# XL4016.net
KiCad netlist of a schematic drawn in Altium Designer
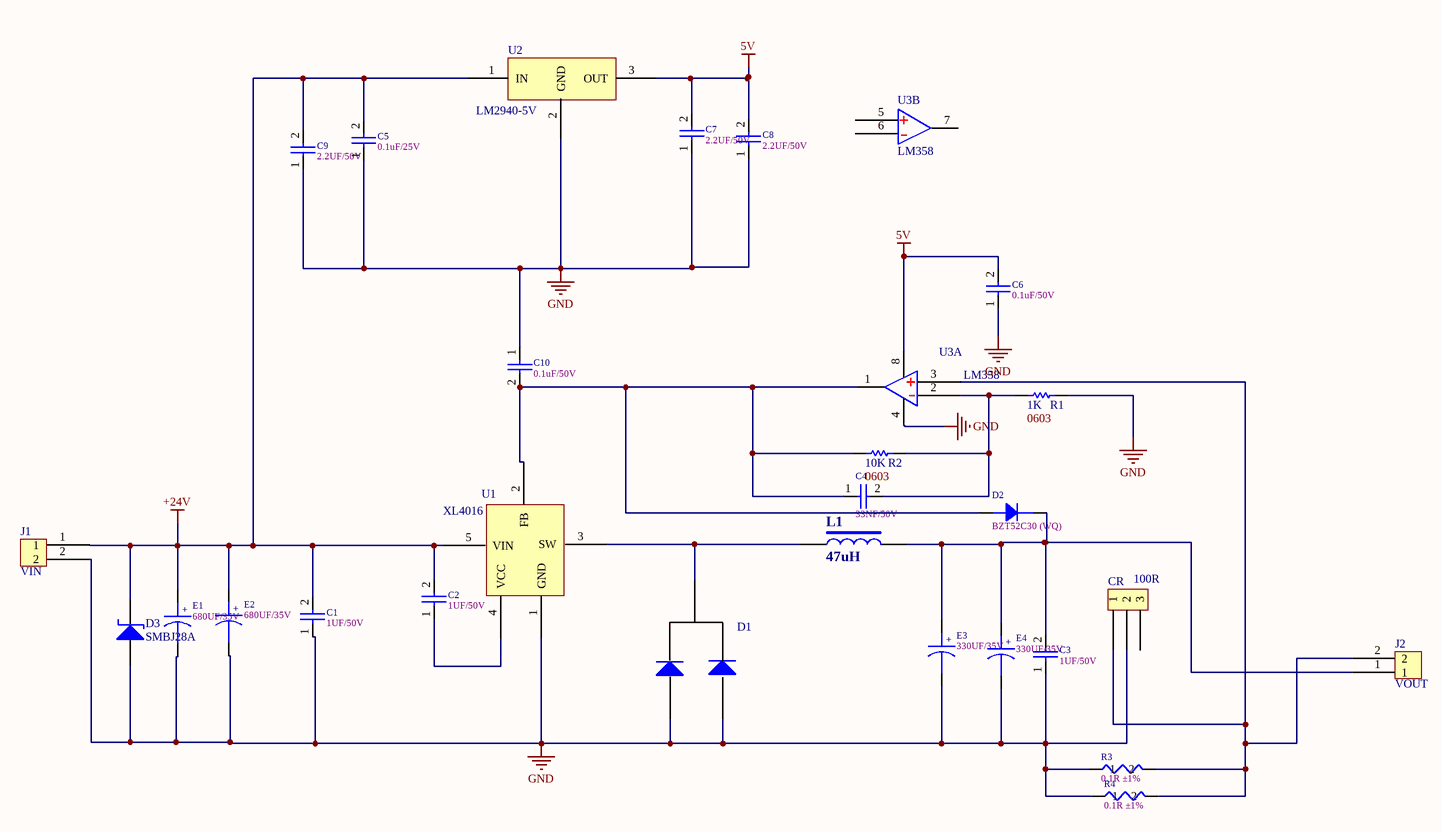
[diagram p0: XL4016.SchDoc]

(export (version "E")
  (design (tool "Eeschema 10.0.6"))
  (components
    (comp (ref "C1")
      (value "1UF/50V")
      (footprint "C0805")
      (description "Capacitor")
      (libsource (lib "清洗机旋钮开关") (part "CAP_5"))
    )
    (comp (ref "C2")
      (value "1UF/50V")
      (footprint "C0805")
      (description "Capacitor")
      (libsource (lib "清洗机旋钮开关") (part "CAP_5"))
    )
    (comp (ref "C3")
      (value "1UF/50V")
      (footprint "C0805")
      (description "Capacitor")
      (libsource (lib "清洗机旋钮开关") (part "CAP_5"))
    )
    (comp (ref "C4")
      (value "33NF/50V")
      (footprint "C0603")
      (description "Capacitor")
      (libsource (lib "清洗机旋钮开关") (part "CAP"))
    )
    (comp (ref "C5")
      (value "0.1uF/25V")
      (footprint "C0603")
      (description "Capacitor")
      (libsource (lib "清洗机旋钮开关") (part "CAP"))
    )
    (comp (ref "C6")
      (value "0.1uF/50V")
      (footprint "C0603")
      (description "Capacitor")
      (libsource (lib "清洗机旋钮开关") (part "CAP"))
    )
    (comp (ref "C7")
      (value "2.2UF/50V")
      (footprint "C0805")
      (description "Capacitor")
      (libsource (lib "清洗机旋钮开关") (part "CAP_5"))
    )
    (comp (ref "C8")
      (value "2.2UF/50V")
      (footprint "C0805")
      (description "Capacitor")
      (libsource (lib "清洗机旋钮开关") (part "CAP_5"))
    )
    (comp (ref "C9")
      (value "2.2UF/50V")
      (footprint "C0805")
      (description "Capacitor")
      (libsource (lib "清洗机旋钮开关") (part "CAP_5"))
    )
    (comp (ref "C10")
      (value "0.1uF/50V")
      (footprint "C0603")
      (description "Capacitor")
      (libsource (lib "清洗机旋钮开关") (part "CAP"))
    )
    (comp (ref "CR") (value "100R") (footprint "3296W") (libsource (lib "VR") (part "RV")))
    (comp (ref "D1") (value "Schottky") (footprint "TO-2520") (libsource (lib "SCHOTTKY") (part "Schottky")))
    (comp (ref "D2")
      (value "BZT52C30 (WQ)")
      (footprint "SOD123")
      (description "Diode")
      (libsource (lib "清洗固化") (part "DIODE._1"))
    )
    (comp (ref "D3") (value "SMBJ28A") (footprint "DO214AA") (libsource (lib "清洗机旋钮开关") (part "TVS")))
    (comp (ref "E1")
      (value "680UF/35V")
      (footprint "C10X17")
      (description "Capacitor")
      (libsource (lib "TL494-BOOST") (part "CAPACITOR POL"))
    )
    (comp (ref "E2")
      (value "680UF/35V")
      (footprint "C10X17")
      (description "Capacitor")
      (libsource (lib "TL494-BOOST") (part "CAPACITOR POL"))
    )
    (comp (ref "E3")
      (value "330UF/35V")
      (footprint "C10X17")
      (description "Capacitor")
      (libsource (lib "TL494-BOOST") (part "CAPACITOR POL"))
    )
    (comp (ref "E4")
      (value "330UF/35V")
      (footprint "C10X17")
      (description "Capacitor")
      (libsource (lib "TL494-BOOST") (part "CAPACITOR POL"))
    )
    (comp (ref "J1") (value "VIN") (footprint "VH3.96_2WP") (libsource (lib "") (part "VH3.96_2P_1")))
    (comp (ref "J2")
      (value "VOUT")
      (footprint "VH3.96_2WP")
      (libsource (lib "VVH3.96_2P") (part "VH3.96_2P"))
    )
    (comp (ref "L1") (value "47uH") (footprint "L24x10") (libsource (lib "清洗机旋钮开关") (part "INDUCTOR2")))
    (comp (ref "R1")
      (value "1K")
      (footprint "0603")
      (description "Resistor")
      (fields (field (name "PUBLISHER") "Altium Limited"))
      (libsource (lib "清洗机旋钮开关") (part "Res1_4"))
    )
    (comp (ref "R2")
      (value "10K")
      (footprint "0603")
      (description "Resistor")
      (fields (field (name "PUBLISHER") "Altium Limited"))
      (libsource (lib "清洗机旋钮开关") (part "Res1_4"))
    )
    (comp (ref "R3")
      (value "0.1R ±1%")
      (footprint "R1206")
      (libsource (lib "MARS2-PRO20201214") (part "RES"))
    )
    (comp (ref "R4")
      (value "0.1R ±1%")
      (footprint "R1206")
      (libsource (lib "MARS2-PRO20201214") (part "RES"))
    )
    (comp (ref "U1") (value "XL4016") (footprint "TO220-5L") (libsource (lib "XL4016") (part "XL4016")))
    (comp (ref "U2")
      (value "LM2940-5V")
      (footprint "SOT-223")
      (libsource (lib "LM2940-5V") (part "LM2940-5V"))
    )
    (comp (ref "U3") (value "LM358") (footprint "SOP8L") (libsource (lib "LM358D") (part "LM358")))
  )
  (nets
    (net (code "1") (name "+24V") (class "Default")
      (node (ref "C1") (pin "2") (pinfunction "2_2") (pintype "passive"))
      (node (ref "C2") (pin "2") (pinfunction "2_2") (pintype "passive"))
      (node (ref "C5") (pin "2") (pinfunction "2_2") (pintype "passive"))
      (node (ref "C9") (pin "2") (pinfunction "2_2") (pintype "passive"))
      (node (ref "D3") (pin "2") (pinfunction "K_2") (pintype "passive"))
      (node (ref "E1") (pin "1") (pinfunction "1_1") (pintype "passive"))
      (node (ref "E2") (pin "1") (pinfunction "1_1") (pintype "passive"))
      (node (ref "J1") (pin "1") (pinfunction "1_1") (pintype "passive"))
      (node (ref "U1") (pin "5") (pinfunction "VIN_5") (pintype "passive"))
      (node (ref "U2") (pin "1") (pinfunction "IN_1") (pintype "passive"))
    )
    (net (code "2") (name "5V") (class "Default")
      (node (ref "C6") (pin "2") (pinfunction "2_2") (pintype "passive"))
      (node (ref "C7") (pin "2") (pinfunction "2_2") (pintype "passive"))
      (node (ref "C8") (pin "2") (pinfunction "2_2") (pintype "passive"))
      (node (ref "U2") (pin "3") (pinfunction "OUT_3") (pintype "passive"))
      (node (ref "U3") (pin "8") (pinfunction "8_8") (pintype "passive"))
    )
    (net (code "3") (name "GND") (class "Default")
      (node (ref "C1") (pin "1") (pinfunction "1_1") (pintype "passive"))
      (node (ref "C10") (pin "1") (pinfunction "1_1") (pintype "passive"))
      (node (ref "C3") (pin "1") (pinfunction "1_1") (pintype "passive"))
      (node (ref "C5") (pin "1") (pinfunction "1_1") (pintype "passive"))
      (node (ref "C6") (pin "1") (pinfunction "1_1") (pintype "passive"))
      (node (ref "C7") (pin "1") (pinfunction "1_1") (pintype "passive"))
      (node (ref "C8") (pin "1") (pinfunction "1_1") (pintype "passive"))
      (node (ref "C9") (pin "1") (pinfunction "1_1") (pintype "passive"))
      (node (ref "CR") (pin "2") (pinfunction "2_2") (pintype "passive"))
      (node (ref "D1") (pin "1") (pinfunction "1_1") (pintype "passive"))
      (node (ref "D1") (pin "3") (pinfunction "3_3") (pintype "passive"))
      (node (ref "D3") (pin "1") (pinfunction "A_1") (pintype "passive"))
      (node (ref "E1") (pin "2") (pinfunction "2_2") (pintype "passive"))
      (node (ref "E2") (pin "2") (pinfunction "2_2") (pintype "passive"))
      (node (ref "E3") (pin "2") (pinfunction "2_2") (pintype "passive"))
      (node (ref "E4") (pin "2") (pinfunction "2_2") (pintype "passive"))
      (node (ref "J1") (pin "2") (pinfunction "2_2") (pintype "passive"))
      (node (ref "R1") (pin "2") (pinfunction "2_2") (pintype "passive"))
      (node (ref "R3") (pin "1") (pinfunction "1_1") (pintype "passive"))
      (node (ref "R4") (pin "1") (pinfunction "1_1") (pintype "passive"))
      (node (ref "U1") (pin "1") (pinfunction "GND_1") (pintype "passive"))
      (node (ref "U2") (pin "2") (pinfunction "GND_2") (pintype "passive"))
      (node (ref "U3") (pin "4") (pinfunction "4_4") (pintype "passive"))
    )
    (net (code "4") (name "Net-(C4-Pad2)") (class "Default")
      (node (ref "C4") (pin "2") (pinfunction "2_2") (pintype "passive"))
      (node (ref "R1") (pin "1") (pinfunction "1_1") (pintype "passive"))
      (node (ref "R2") (pin "2") (pinfunction "2_2") (pintype "passive"))
      (node (ref "U3") (pin "2") (pinfunction "2_2") (pintype "passive"))
    )
    (net (code "5") (name "Net-(CR-Pad1)") (class "Default")
      (node (ref "CR") (pin "1") (pinfunction "1_1") (pintype "passive"))
      (node (ref "J2") (pin "2") (pinfunction "2_2") (pintype "passive"))
      (node (ref "R3") (pin "2") (pinfunction "2_2") (pintype "passive"))
      (node (ref "R4") (pin "2") (pinfunction "2_2") (pintype "passive"))
      (node (ref "U3") (pin "3") (pinfunction "3_3") (pintype "passive"))
    )
    (net (code "6") (name "Net-(D2-A)") (class "Default")
      (node (ref "C10") (pin "2") (pinfunction "2_2") (pintype "passive"))
      (node (ref "C4") (pin "1") (pinfunction "1_1") (pintype "passive"))
      (node (ref "D2") (pin "1") (pinfunction "A_1") (pintype "passive"))
      (node (ref "R2") (pin "1") (pinfunction "1_1") (pintype "passive"))
      (node (ref "U1") (pin "2") (pinfunction "FB_2") (pintype "passive"))
      (node (ref "U3") (pin "1") (pinfunction "1_1") (pintype "passive"))
    )
    (net (code "7") (name "Net-(D2-K)") (class "Default")
      (node (ref "C3") (pin "2") (pinfunction "2_2") (pintype "passive"))
      (node (ref "D2") (pin "2") (pinfunction "K_2") (pintype "passive"))
      (node (ref "E3") (pin "1") (pinfunction "1_1") (pintype "passive"))
      (node (ref "E4") (pin "1") (pinfunction "1_1") (pintype "passive"))
      (node (ref "J2") (pin "1") (pinfunction "1_1") (pintype "passive"))
      (node (ref "L1") (pin "2") (pinfunction "2_2") (pintype "passive"))
    )
    (net (code "8") (name "Net-(U1-SW)") (class "Default")
      (node (ref "D1") (pin "2") (pinfunction "2_2") (pintype "passive"))
      (node (ref "L1") (pin "1") (pinfunction "1_1") (pintype "passive"))
      (node (ref "U1") (pin "3") (pinfunction "SW_3") (pintype "passive"))
    )
    (net (code "9") (name "Net-(U1-VCC)") (class "Default")
      (node (ref "C2") (pin "1") (pinfunction "1_1") (pintype "passive"))
      (node (ref "U1") (pin "4") (pinfunction "VCC_4") (pintype "passive"))
    )
    (net (code "10") (name "unconnected-(CR-Pad3)") (class "Default")
      (node (ref "CR") (pin "3") (pinfunction "3_3") (pintype "passive"))
    )
    (net (code "11") (name "unconnected-(U3-Pad5)") (class "Default")
      (node (ref "U3") (pin "5") (pinfunction "5_5") (pintype "passive"))
    )
    (net (code "12") (name "unconnected-(U3-Pad6)") (class "Default")
      (node (ref "U3") (pin "6") (pinfunction "6_6") (pintype "passive"))
    )
    (net (code "13") (name "unconnected-(U3-Pad7)") (class "Default")
      (node (ref "U3") (pin "7") (pinfunction "7_7") (pintype "passive"))
    )
  )
)
